# SPARK.net
KiCad netlist of a schematic drawn in EAGLE
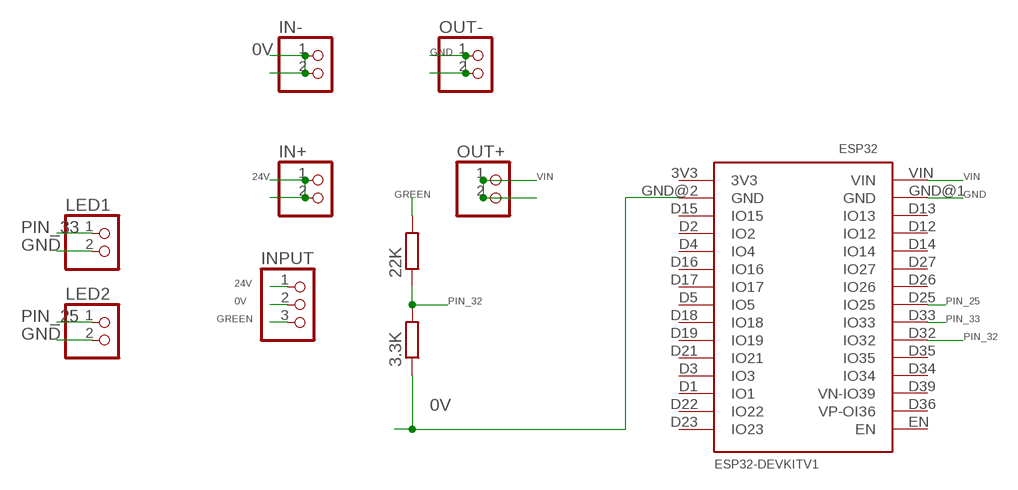
[diagram p0: schematic, sheet 1]

(export (version "E")
  (design (tool "Eeschema 10.0.6"))
  (components
    (comp (ref "3.3K")
      (value "R-EU_0207/10")
      (footprint "eagle-import:0207_10")
      (libsource (lib "eagle-import") (part "R-EU_0207/10"))
    )
    (comp (ref "22K")
      (value "R-EU_0207/10")
      (footprint "eagle-import:0207_10")
      (libsource (lib "eagle-import") (part "R-EU_0207/10"))
    )
    (comp (ref "ESP32")
      (value "ESP32DEVKITV1")
      (footprint "eagle-import:ESP32-DEVKITV1")
      (libsource (lib "eagle-import") (part "ESP32DEVKITV1"))
    )
    (comp (ref "IN+")
      (value "PINHD-1X2")
      (footprint "eagle-import:1X02")
      (libsource (lib "eagle-import") (part "PINHD-1X2"))
    )
    (comp (ref "IN-")
      (value "PINHD-1X2")
      (footprint "eagle-import:1X02")
      (libsource (lib "eagle-import") (part "PINHD-1X2"))
    )
    (comp (ref "INPUT")
      (value "PINHD-1X3")
      (footprint "eagle-import:1X03")
      (libsource (lib "eagle-import") (part "PINHD-1X3"))
    )
    (comp (ref "LED1")
      (value "PINHD-1X2")
      (footprint "eagle-import:1X02")
      (libsource (lib "eagle-import") (part "PINHD-1X2"))
    )
    (comp (ref "LED2")
      (value "PINHD-1X2")
      (footprint "eagle-import:1X02")
      (libsource (lib "eagle-import") (part "PINHD-1X2"))
    )
    (comp (ref "OUT+")
      (value "PINHD-1X2")
      (footprint "eagle-import:1X02")
      (libsource (lib "eagle-import") (part "PINHD-1X2"))
    )
    (comp (ref "OUT-")
      (value "PINHD-1X2")
      (footprint "eagle-import:1X02")
      (libsource (lib "eagle-import") (part "PINHD-1X2"))
    )
  )
  (nets
    (net (code "1") (name "/0V") (class "Default")
      (node (ref "3.3K") (pin "1") (pinfunction "1_1") (pintype "passive"))
      (node (ref "ESP32") (pin "GND@2") (pinfunction "GND_GND@2") (pintype "bidirectional"))
      (node (ref "IN-") (pin "1") (pinfunction "1_1") (pintype "passive"))
      (node (ref "IN-") (pin "2") (pinfunction "2_2") (pintype "passive"))
      (node (ref "INPUT") (pin "2") (pinfunction "2_2") (pintype "passive"))
    )
    (net (code "2") (name "/24V") (class "Default")
      (node (ref "IN+") (pin "1") (pinfunction "1_1") (pintype "passive"))
      (node (ref "IN+") (pin "2") (pinfunction "2_2") (pintype "passive"))
      (node (ref "INPUT") (pin "1") (pinfunction "1_1") (pintype "passive"))
    )
    (net (code "3") (name "/GND") (class "Default")
      (node (ref "ESP32") (pin "GND@1") (pinfunction "GND_GND@1") (pintype "bidirectional"))
      (node (ref "LED1") (pin "2") (pinfunction "2_2") (pintype "passive"))
      (node (ref "LED2") (pin "2") (pinfunction "2_2") (pintype "passive"))
      (node (ref "OUT-") (pin "1") (pinfunction "1_1") (pintype "passive"))
      (node (ref "OUT-") (pin "2") (pinfunction "2_2") (pintype "passive"))
    )
    (net (code "4") (name "/GREEN") (class "Default")
      (node (ref "22K") (pin "2") (pinfunction "2_2") (pintype "passive"))
      (node (ref "INPUT") (pin "3") (pinfunction "3_3") (pintype "passive"))
    )
    (net (code "5") (name "/PIN_25") (class "Default")
      (node (ref "ESP32") (pin "D25") (pinfunction "IO25_D25") (pintype "bidirectional"))
      (node (ref "LED2") (pin "1") (pinfunction "1_1") (pintype "passive"))
    )
    (net (code "6") (name "/PIN_32") (class "Default")
      (node (ref "22K") (pin "1") (pinfunction "1_1") (pintype "passive"))
      (node (ref "3.3K") (pin "2") (pinfunction "2_2") (pintype "passive"))
      (node (ref "ESP32") (pin "D32") (pinfunction "IO32_D32") (pintype "bidirectional"))
    )
    (net (code "7") (name "/PIN_33") (class "Default")
      (node (ref "ESP32") (pin "D33") (pinfunction "IO33_D33") (pintype "bidirectional"))
      (node (ref "LED1") (pin "1") (pinfunction "1_1") (pintype "passive"))
    )
    (net (code "8") (name "/VIN") (class "Default")
      (node (ref "ESP32") (pin "VIN") (pinfunction "VIN_VIN") (pintype "bidirectional"))
      (node (ref "OUT+") (pin "1") (pinfunction "1_1") (pintype "passive"))
      (node (ref "OUT+") (pin "2") (pinfunction "2_2") (pintype "passive"))
    )
    (net (code "9") (name "unconnected-(ESP32-IO1-PadD1)") (class "Default")
      (node (ref "ESP32") (pin "D1") (pinfunction "IO1_D1") (pintype "bidirectional"))
    )
    (net (code "10") (name "unconnected-(ESP32-IO2-PadD2)") (class "Default")
      (node (ref "ESP32") (pin "D2") (pinfunction "IO2_D2") (pintype "bidirectional"))
    )
    (net (code "11") (name "unconnected-(ESP32-IO3-PadD3)") (class "Default")
      (node (ref "ESP32") (pin "D3") (pinfunction "IO3_D3") (pintype "bidirectional"))
    )
    (net (code "12") (name "unconnected-(ESP32-IO4-PadD4)") (class "Default")
      (node (ref "ESP32") (pin "D4") (pinfunction "IO4_D4") (pintype "bidirectional"))
    )
    (net (code "13") (name "unconnected-(ESP32-IO5-PadD5)") (class "Default")
      (node (ref "ESP32") (pin "D5") (pinfunction "IO5_D5") (pintype "bidirectional"))
    )
    (net (code "14") (name "unconnected-(ESP32-IO12-PadD12)") (class "Default")
      (node (ref "ESP32") (pin "D12") (pinfunction "IO12_D12") (pintype "bidirectional"))
    )
    (net (code "15") (name "unconnected-(ESP32-IO13-PadD13)") (class "Default")
      (node (ref "ESP32") (pin "D13") (pinfunction "IO13_D13") (pintype "bidirectional"))
    )
    (net (code "16") (name "unconnected-(ESP32-IO14-PadD14)") (class "Default")
      (node (ref "ESP32") (pin "D14") (pinfunction "IO14_D14") (pintype "bidirectional"))
    )
    (net (code "17") (name "unconnected-(ESP32-IO15-PadD15)") (class "Default")
      (node (ref "ESP32") (pin "D15") (pinfunction "IO15_D15") (pintype "bidirectional"))
    )
    (net (code "18") (name "unconnected-(ESP32-IO16-PadD16)") (class "Default")
      (node (ref "ESP32") (pin "D16") (pinfunction "IO16_D16") (pintype "bidirectional"))
    )
    (net (code "19") (name "unconnected-(ESP32-IO17-PadD17)") (class "Default")
      (node (ref "ESP32") (pin "D17") (pinfunction "IO17_D17") (pintype "bidirectional"))
    )
    (net (code "20") (name "unconnected-(ESP32-IO18-PadD18)") (class "Default")
      (node (ref "ESP32") (pin "D18") (pinfunction "IO18_D18") (pintype "bidirectional"))
    )
    (net (code "21") (name "unconnected-(ESP32-IO19-PadD19)") (class "Default")
      (node (ref "ESP32") (pin "D19") (pinfunction "IO19_D19") (pintype "bidirectional"))
    )
    (net (code "22") (name "unconnected-(ESP32-IO21-PadD21)") (class "Default")
      (node (ref "ESP32") (pin "D21") (pinfunction "IO21_D21") (pintype "bidirectional"))
    )
    (net (code "23") (name "unconnected-(ESP32-IO22-PadD22)") (class "Default")
      (node (ref "ESP32") (pin "D22") (pinfunction "IO22_D22") (pintype "bidirectional"))
    )
    (net (code "24") (name "unconnected-(ESP32-IO23-PadD23)") (class "Default")
      (node (ref "ESP32") (pin "D23") (pinfunction "IO23_D23") (pintype "bidirectional"))
    )
    (net (code "25") (name "unconnected-(ESP32-IO26-PadD26)") (class "Default")
      (node (ref "ESP32") (pin "D26") (pinfunction "IO26_D26") (pintype "bidirectional"))
    )
    (net (code "26") (name "unconnected-(ESP32-IO27-PadD27)") (class "Default")
      (node (ref "ESP32") (pin "D27") (pinfunction "IO27_D27") (pintype "bidirectional"))
    )
    (net (code "27") (name "unconnected-(ESP32-IO34-PadD34)") (class "Default")
      (node (ref "ESP32") (pin "D34") (pinfunction "IO34_D34") (pintype "bidirectional"))
    )
    (net (code "28") (name "unconnected-(ESP32-IO35-PadD35)") (class "Default")
      (node (ref "ESP32") (pin "D35") (pinfunction "IO35_D35") (pintype "bidirectional"))
    )
    (net (code "29") (name "unconnected-(ESP32-Pad3V3)") (class "Default")
      (node (ref "ESP32") (pin "3V3") (pinfunction "3V3_3V3") (pintype "bidirectional"))
    )
    (net (code "30") (name "unconnected-(ESP32-PadEN)") (class "Default")
      (node (ref "ESP32") (pin "EN") (pinfunction "EN_EN") (pintype "bidirectional"))
    )
    (net (code "31") (name "unconnected-(ESP32-VN-IO39-PadD39)") (class "Default")
      (node (ref "ESP32") (pin "D39") (pinfunction "VN-IO39_D39") (pintype "bidirectional"))
    )
    (net (code "32") (name "unconnected-(ESP32-VP-OI36-PadD36)") (class "Default")
      (node (ref "ESP32") (pin "D36") (pinfunction "VP-OI36_D36") (pintype "bidirectional"))
    )
  )
)
